# ArduOSD_Simple2222.net
KiCad netlist of a schematic drawn in EAGLE
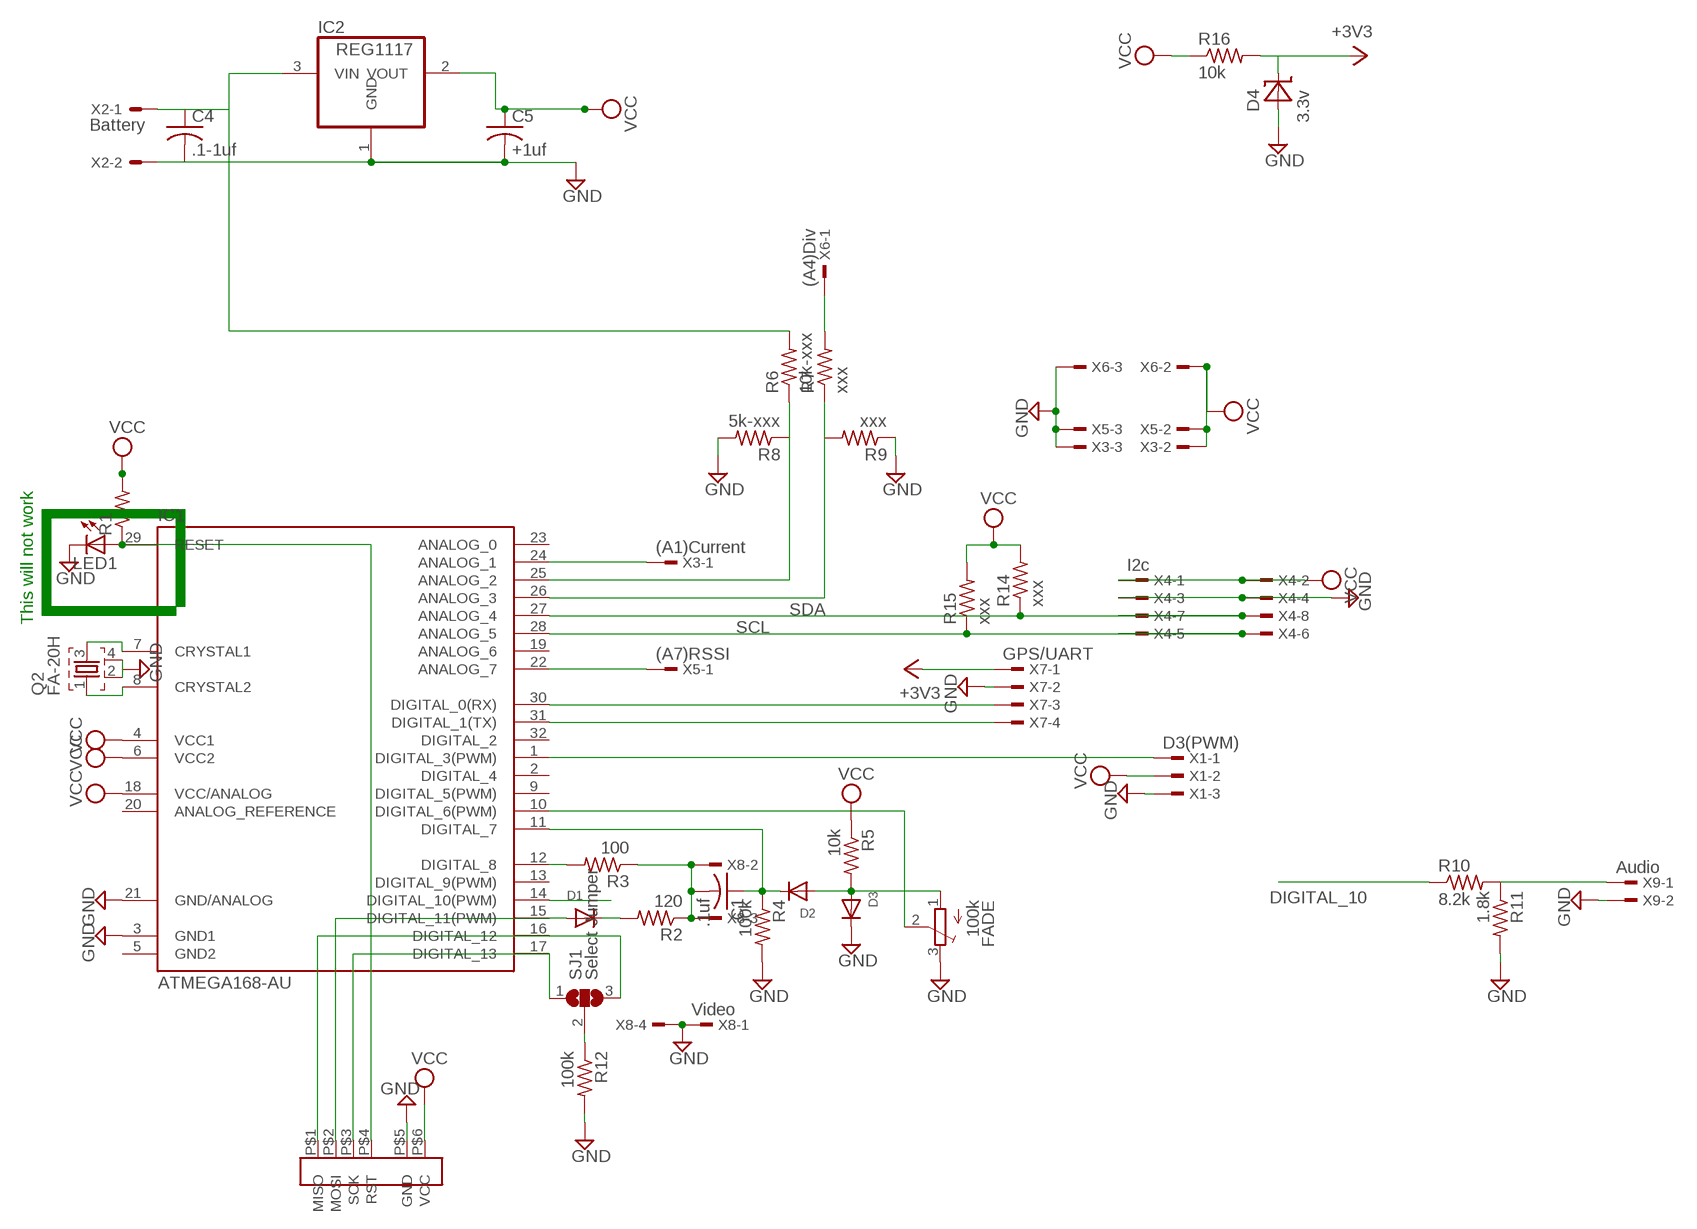
[diagram p0: schematic, sheet 1]

(export (version "E")
  (design (tool "Eeschema 10.0.6"))
  (components
    (comp (ref "C1")
      (value ".1uf")
      (footprint "eagle-import:C0805K")
      (libsource (lib "eagle-import") (part "C-USC0805K"))
    )
    (comp (ref "C4")
      (value ".1-1uf")
      (footprint "eagle-import:C0805K")
      (libsource (lib "eagle-import") (part "C-USC0805K"))
    )
    (comp (ref "C5")
      (value "+1uf")
      (footprint "eagle-import:C0805K")
      (libsource (lib "eagle-import") (part "C-USC0805K"))
    )
    (comp (ref "D1")
      (value "DIODESOT23_WAVE")
      (footprint "eagle-import:SOT23-W")
      (libsource (lib "eagle-import") (part "DIODESOT23_WAVE"))
    )
    (comp (ref "D2")
      (value "DIODESOT23_WAVE")
      (footprint "eagle-import:SOT23-W")
      (libsource (lib "eagle-import") (part "DIODESOT23_WAVE"))
    )
    (comp (ref "D3")
      (value "DIODESOT23_WAVE")
      (footprint "eagle-import:SOT23-W")
      (libsource (lib "eagle-import") (part "DIODESOT23_WAVE"))
    )
    (comp (ref "D4")
      (value "3.3v")
      (footprint "eagle-import:SOD-123")
      (libsource (lib "eagle-import") (part "ZENER_SOD123"))
    )
    (comp (ref "FADE")
      (value "100k")
      (footprint "eagle-import:TC33X")
      (libsource (lib "eagle-import") (part "TRIMPOTTC33X"))
    )
    (comp (ref "IC1")
      (value "ATMEGA168-AU")
      (footprint "eagle-import:TQFP32-08")
      (libsource (lib "eagle-import") (part "ATMEGA168-AU"))
    )
    (comp (ref "IC2")
      (value "REG1117")
      (footprint "eagle-import:SOT223")
      (libsource (lib "eagle-import") (part "REG1117"))
    )
    (comp (ref "LED1")
      (value "LEDCHIP-LED0805")
      (footprint "eagle-import:CHIP-LED0805")
      (libsource (lib "eagle-import") (part "LEDCHIP-LED0805"))
    )
    (comp (ref "Q2")
      (value "FA-20H")
      (footprint "eagle-import:FA-20H")
      (libsource (lib "eagle-import") (part "FA-20H"))
    )
    (comp (ref "R1")
      (value "R-US_R0805")
      (footprint "eagle-import:R0805")
      (libsource (lib "eagle-import") (part "R-US_R0805"))
    )
    (comp (ref "R2")
      (value "120")
      (footprint "eagle-import:R0805")
      (libsource (lib "eagle-import") (part "R-US_R0805"))
    )
    (comp (ref "R3")
      (value "100")
      (footprint "eagle-import:R0805")
      (libsource (lib "eagle-import") (part "R-US_R0805"))
    )
    (comp (ref "R4")
      (value "100k")
      (footprint "eagle-import:R0805")
      (libsource (lib "eagle-import") (part "R-US_R0805"))
    )
    (comp (ref "R5")
      (value "10k")
      (footprint "eagle-import:R0805")
      (libsource (lib "eagle-import") (part "R-US_R0805"))
    )
    (comp (ref "R6")
      (value "10k-xxx")
      (footprint "eagle-import:R0805")
      (libsource (lib "eagle-import") (part "R-US_R0805"))
    )
    (comp (ref "R7")
      (value "xxx")
      (footprint "eagle-import:R0805")
      (libsource (lib "eagle-import") (part "R-US_R0805"))
    )
    (comp (ref "R8")
      (value "5k-xxx")
      (footprint "eagle-import:R0805")
      (libsource (lib "eagle-import") (part "R-US_R0805"))
    )
    (comp (ref "R9")
      (value "xxx")
      (footprint "eagle-import:R0805")
      (libsource (lib "eagle-import") (part "R-US_R0805"))
    )
    (comp (ref "R10")
      (value "8.2k")
      (footprint "eagle-import:R0805")
      (libsource (lib "eagle-import") (part "R-US_R0805"))
    )
    (comp (ref "R11")
      (value "1.8k")
      (footprint "eagle-import:R0805")
      (libsource (lib "eagle-import") (part "R-US_R0805"))
    )
    (comp (ref "R12")
      (value "100k")
      (footprint "eagle-import:R0805")
      (libsource (lib "eagle-import") (part "R-US_R0805"))
    )
    (comp (ref "R14")
      (value "xxx")
      (footprint "eagle-import:R0805")
      (libsource (lib "eagle-import") (part "R-US_R0805"))
    )
    (comp (ref "R15")
      (value "xxx")
      (footprint "eagle-import:R0805")
      (libsource (lib "eagle-import") (part "R-US_R0805"))
    )
    (comp (ref "R16")
      (value "10k")
      (footprint "eagle-import:R0805")
      (libsource (lib "eagle-import") (part "R-US_R0805"))
    )
    (comp (ref "SJ1")
      (value "Select Jumper")
      (footprint "eagle-import:SJ_2")
      (libsource (lib "eagle-import") (part "SJ2W"))
    )
    (comp (ref "U$1")
      (value "LIN_ISP")
      (footprint "eagle-import:LINEAR_ISP")
      (libsource (lib "eagle-import") (part "LIN_ISP"))
    )
    (comp (ref "X1")
      (value "D3(PWM)")
      (footprint "eagle-import:TSW-103-02-S-S")
      (fields (field (name "OC_FARNELL") "unknown") (field (name "OC_NEWARK") "unknown"))
      (libsource (lib "eagle-import") (part "TSW-103-02-S-S"))
    )
    (comp (ref "X2")
      (value "Battery")
      (footprint "eagle-import:22-23-2021")
      (fields (field (name "MF") "MOLEX") (field (name "MPN") "22-23-2021"))
      (libsource (lib "eagle-import") (part "22-23-2021"))
    )
    (comp (ref "X3")
      (value "(A1)Current")
      (footprint "eagle-import:TSW-103-02-S-S")
      (libsource (lib "eagle-import") (part "TSW-103-02-S-S"))
    )
    (comp (ref "X4")
      (value "I2c")
      (footprint "eagle-import:TSW-104-02-S-D-RA")
      (libsource (lib "eagle-import") (part "TSW-104-02-S-D-RA"))
    )
    (comp (ref "X5")
      (value "(A7)RSSI")
      (footprint "eagle-import:TSW-103-02-S-S")
      (libsource (lib "eagle-import") (part "TSW-103-02-S-S"))
    )
    (comp (ref "X6")
      (value "(A4)Div")
      (footprint "eagle-import:TSW-103-02-S-S")
      (fields (field (name "OC_FARNELL") "unknown") (field (name "OC_NEWARK") "unknown"))
      (libsource (lib "eagle-import") (part "TSW-103-02-S-S"))
    )
    (comp (ref "X7")
      (value "GPS/UART")
      (footprint "eagle-import:TSW-104-02-S-S-RA")
      (libsource (lib "eagle-import") (part "TSW-104-02-S-S-RA"))
    )
    (comp (ref "X8")
      (value "Video")
      (footprint "eagle-import:TSW-104-02-S-S-RA")
      (libsource (lib "eagle-import") (part "TSW-104-02-S-S-RA"))
    )
    (comp (ref "X9")
      (value "Audio")
      (footprint "eagle-import:TSW-102-02-S-S-RA")
      (fields (field (name "OC_FARNELL") "unknown") (field (name "OC_NEWARK") "unknown"))
      (libsource (lib "eagle-import") (part "TSW-102-02-S-S-RA"))
    )
  )
  (nets
    (net (code "1") (name "+3V3") (class "Default")
      (node (ref "D4") (pin "1") (pinfunction "C_1") (pintype "passive"))
      (node (ref "R16") (pin "2") (pinfunction "2_2") (pintype "passive"))
      (node (ref "X7") (pin "1") (pinfunction "1_1") (pintype "passive"))
    )
    (net (code "2") (name "/DIGITAL_10") (class "Default")
      (node (ref "IC1") (pin "14") (pinfunction "DIGITAL_10(PWM)_14") (pintype "bidirectional"))
      (node (ref "R10") (pin "1") (pinfunction "1_1") (pintype "passive"))
    )
    (net (code "3") (name "/GND2") (class "Default")
      (node (ref "IC1") (pin "5") (pinfunction "GND2_5") (pintype "power_in"))
    )
    (net (code "4") (name "/SCL") (class "Default")
      (node (ref "IC1") (pin "28") (pinfunction "ANALOG_5_28") (pintype "bidirectional"))
      (node (ref "R15") (pin "1") (pinfunction "1_1") (pintype "passive"))
      (node (ref "X4") (pin "5") (pinfunction "1_5") (pintype "passive"))
      (node (ref "X4") (pin "6") (pinfunction "1_6") (pintype "passive"))
    )
    (net (code "5") (name "/SDA") (class "Default")
      (node (ref "IC1") (pin "27") (pinfunction "ANALOG_4_27") (pintype "bidirectional"))
      (node (ref "R14") (pin "1") (pinfunction "1_1") (pintype "passive"))
      (node (ref "X4") (pin "7") (pinfunction "1_7") (pintype "passive"))
      (node (ref "X4") (pin "8") (pinfunction "1_8") (pintype "passive"))
    )
    (net (code "6") (name "GND") (class "Default")
      (node (ref "C4") (pin "2") (pinfunction "2_2") (pintype "passive"))
      (node (ref "C5") (pin "2") (pinfunction "2_2") (pintype "passive"))
      (node (ref "D3") (pin "3") (pinfunction "C_3") (pintype "passive"))
      (node (ref "D4") (pin "2") (pinfunction "A_2") (pintype "passive"))
      (node (ref "FADE") (pin "3") (pinfunction "E_3") (pintype "passive"))
      (node (ref "IC1") (pin "21") (pinfunction "GND/ANALOG_21") (pintype "power_in"))
      (node (ref "IC1") (pin "3") (pinfunction "GND1_3") (pintype "power_in"))
      (node (ref "IC2") (pin "1") (pinfunction "GND_1") (pintype "power_in"))
      (node (ref "LED1") (pin "C") (pinfunction "C_C") (pintype "passive"))
      (node (ref "Q2") (pin "2") (pinfunction "2_2") (pintype "passive"))
      (node (ref "Q2") (pin "4") (pinfunction "4_4") (pintype "passive"))
      (node (ref "R11") (pin "2") (pinfunction "2_2") (pintype "passive"))
      (node (ref "R12") (pin "2") (pinfunction "2_2") (pintype "passive"))
      (node (ref "R4") (pin "2") (pinfunction "2_2") (pintype "passive"))
      (node (ref "R8") (pin "2") (pinfunction "2_2") (pintype "passive"))
      (node (ref "R9") (pin "1") (pinfunction "1_1") (pintype "passive"))
      (node (ref "U$1") (pin "P$5") (pinfunction "GND_P$5") (pintype "bidirectional"))
      (node (ref "X1") (pin "3") (pinfunction "1_3") (pintype "passive"))
      (node (ref "X2") (pin "2") (pinfunction "S_2") (pintype "passive"))
      (node (ref "X3") (pin "3") (pinfunction "1_3") (pintype "passive"))
      (node (ref "X4") (pin "3") (pinfunction "1_3") (pintype "passive"))
      (node (ref "X4") (pin "4") (pinfunction "1_4") (pintype "passive"))
      (node (ref "X5") (pin "3") (pinfunction "1_3") (pintype "passive"))
      (node (ref "X6") (pin "3") (pinfunction "1_3") (pintype "passive"))
      (node (ref "X7") (pin "2") (pinfunction "1_2") (pintype "passive"))
      (node (ref "X8") (pin "1") (pinfunction "1_1") (pintype "passive"))
      (node (ref "X8") (pin "4") (pinfunction "1_4") (pintype "passive"))
      (node (ref "X9") (pin "2") (pinfunction "1_2") (pintype "passive"))
    )
    (net (code "7") (name "Net-(D1-A)") (class "Default")
      (node (ref "D1") (pin "1") (pinfunction "A_1") (pintype "passive"))
      (node (ref "IC1") (pin "15") (pinfunction "DIGITAL_11(PWM)_15") (pintype "bidirectional"))
      (node (ref "U$1") (pin "P$2") (pinfunction "MOSI_P$2") (pintype "bidirectional"))
    )
    (net (code "8") (name "Net-(D1-C)") (class "Default")
      (node (ref "D1") (pin "3") (pinfunction "C_3") (pintype "passive"))
      (node (ref "R2") (pin "2") (pinfunction "2_2") (pintype "passive"))
    )
    (net (code "9") (name "Net-(D2-A)") (class "Default")
      (node (ref "D2") (pin "1") (pinfunction "A_1") (pintype "passive"))
      (node (ref "D3") (pin "1") (pinfunction "A_1") (pintype "passive"))
      (node (ref "FADE") (pin "1") (pinfunction "A_1") (pintype "passive"))
      (node (ref "R5") (pin "2") (pinfunction "2_2") (pintype "passive"))
    )
    (net (code "10") (name "Net-(D2-C)") (class "Default")
      (node (ref "C1") (pin "1") (pinfunction "1_1") (pintype "passive"))
      (node (ref "D2") (pin "3") (pinfunction "C_3") (pintype "passive"))
      (node (ref "IC1") (pin "11") (pinfunction "DIGITAL_7_11") (pintype "bidirectional"))
      (node (ref "R4") (pin "1") (pinfunction "1_1") (pintype "passive"))
    )
    (net (code "11") (name "Net-(FADE-S)") (class "Default")
      (node (ref "FADE") (pin "2") (pinfunction "S_2") (pintype "passive"))
      (node (ref "IC1") (pin "10") (pinfunction "DIGITAL_6(PWM)_10") (pintype "bidirectional"))
    )
    (net (code "12") (name "Net-(IC1-ANALOG_1)") (class "Default")
      (node (ref "IC1") (pin "24") (pinfunction "ANALOG_1_24") (pintype "bidirectional"))
      (node (ref "X3") (pin "1") (pinfunction "1_1") (pintype "passive"))
    )
    (net (code "13") (name "Net-(IC1-ANALOG_2)") (class "Default")
      (node (ref "IC1") (pin "25") (pinfunction "ANALOG_2_25") (pintype "bidirectional"))
      (node (ref "R6") (pin "1") (pinfunction "1_1") (pintype "passive"))
      (node (ref "R8") (pin "1") (pinfunction "1_1") (pintype "passive"))
    )
    (net (code "14") (name "Net-(IC1-ANALOG_3)") (class "Default")
      (node (ref "IC1") (pin "26") (pinfunction "ANALOG_3_26") (pintype "bidirectional"))
      (node (ref "R7") (pin "1") (pinfunction "1_1") (pintype "passive"))
      (node (ref "R9") (pin "2") (pinfunction "2_2") (pintype "passive"))
    )
    (net (code "15") (name "Net-(IC1-ANALOG_7)") (class "Default")
      (node (ref "IC1") (pin "22") (pinfunction "ANALOG_7_22") (pintype "passive"))
      (node (ref "X5") (pin "1") (pinfunction "1_1") (pintype "passive"))
    )
    (net (code "16") (name "Net-(IC1-CRYSTAL1)") (class "Default")
      (node (ref "IC1") (pin "7") (pinfunction "CRYSTAL1_7") (pintype "bidirectional"))
      (node (ref "Q2") (pin "3") (pinfunction "3_3") (pintype "passive"))
    )
    (net (code "17") (name "Net-(IC1-CRYSTAL2)") (class "Default")
      (node (ref "IC1") (pin "8") (pinfunction "CRYSTAL2_8") (pintype "bidirectional"))
      (node (ref "Q2") (pin "1") (pinfunction "1_1") (pintype "passive"))
    )
    (net (code "18") (name "Net-(IC1-DIGITAL_0(RX))") (class "Default")
      (node (ref "IC1") (pin "30") (pinfunction "DIGITAL_0(RX)_30") (pintype "bidirectional"))
      (node (ref "X7") (pin "3") (pinfunction "1_3") (pintype "passive"))
    )
    (net (code "19") (name "Net-(IC1-DIGITAL_1(TX))") (class "Default")
      (node (ref "IC1") (pin "31") (pinfunction "DIGITAL_1(TX)_31") (pintype "bidirectional"))
      (node (ref "X7") (pin "4") (pinfunction "1_4") (pintype "passive"))
    )
    (net (code "20") (name "Net-(IC1-DIGITAL_3(PWM))") (class "Default")
      (node (ref "IC1") (pin "1") (pinfunction "DIGITAL_3(PWM)_1") (pintype "bidirectional"))
      (node (ref "X1") (pin "1") (pinfunction "1_1") (pintype "passive"))
    )
    (net (code "21") (name "Net-(IC1-DIGITAL_8)") (class "Default")
      (node (ref "IC1") (pin "12") (pinfunction "DIGITAL_8_12") (pintype "bidirectional"))
      (node (ref "R3") (pin "2") (pinfunction "2_2") (pintype "passive"))
    )
    (net (code "22") (name "Net-(IC1-DIGITAL_12)") (class "Default")
      (node (ref "IC1") (pin "16") (pinfunction "DIGITAL_12_16") (pintype "bidirectional"))
      (node (ref "SJ1") (pin "3") (pinfunction "3_3") (pintype "passive"))
      (node (ref "U$1") (pin "P$1") (pinfunction "MISO_P$1") (pintype "bidirectional"))
    )
    (net (code "23") (name "Net-(IC1-DIGITAL_13)") (class "Default")
      (node (ref "IC1") (pin "17") (pinfunction "DIGITAL_13_17") (pintype "bidirectional"))
      (node (ref "SJ1") (pin "1") (pinfunction "1_1") (pintype "passive"))
      (node (ref "U$1") (pin "P$3") (pinfunction "SCK_P$3") (pintype "bidirectional"))
    )
    (net (code "24") (name "Net-(IC1-RESET)") (class "Default")
      (node (ref "IC1") (pin "29") (pinfunction "RESET_29") (pintype "bidirectional"))
      (node (ref "LED1") (pin "A") (pinfunction "A_A") (pintype "passive"))
      (node (ref "R1") (pin "1") (pinfunction "1_1") (pintype "passive"))
      (node (ref "U$1") (pin "P$4") (pinfunction "RST_P$4") (pintype "bidirectional"))
    )
    (net (code "25") (name "Net-(IC2-VIN)") (class "Default")
      (node (ref "C4") (pin "1") (pinfunction "1_1") (pintype "passive"))
      (node (ref "IC2") (pin "3") (pinfunction "VIN_3") (pintype "input"))
      (node (ref "R6") (pin "2") (pinfunction "2_2") (pintype "passive"))
      (node (ref "X2") (pin "1") (pinfunction "S_1") (pintype "passive"))
    )
    (net (code "26") (name "Net-(R7-Pad2)") (class "Default")
      (node (ref "R7") (pin "2") (pinfunction "2_2") (pintype "passive"))
      (node (ref "X6") (pin "1") (pinfunction "1_1") (pintype "passive"))
    )
    (net (code "27") (name "Net-(R10-Pad2)") (class "Default")
      (node (ref "R10") (pin "2") (pinfunction "2_2") (pintype "passive"))
      (node (ref "R11") (pin "1") (pinfunction "1_1") (pintype "passive"))
      (node (ref "X9") (pin "1") (pinfunction "1_1") (pintype "passive"))
    )
    (net (code "28") (name "Net-(R12-Pad1)") (class "Default")
      (node (ref "R12") (pin "1") (pinfunction "1_1") (pintype "passive"))
      (node (ref "SJ1") (pin "2") (pinfunction "2_2") (pintype "passive"))
    )
    (net (code "29") (name "Net-(X8B-1)") (class "Default")
      (node (ref "C1") (pin "2") (pinfunction "2_2") (pintype "passive"))
      (node (ref "R2") (pin "1") (pinfunction "1_1") (pintype "passive"))
      (node (ref "R3") (pin "1") (pinfunction "1_1") (pintype "passive"))
      (node (ref "X8") (pin "2") (pinfunction "1_2") (pintype "passive"))
      (node (ref "X8") (pin "3") (pinfunction "1_3") (pintype "passive"))
    )
    (net (code "30") (name "VCC") (class "Default")
      (node (ref "C5") (pin "1") (pinfunction "1_1") (pintype "passive"))
      (node (ref "IC1") (pin "18") (pinfunction "VCC/ANALOG_18") (pintype "passive"))
      (node (ref "IC1") (pin "4") (pinfunction "VCC1_4") (pintype "power_in"))
      (node (ref "IC1") (pin "6") (pinfunction "VCC2_6") (pintype "power_in"))
      (node (ref "IC2") (pin "2") (pinfunction "VOUT_2") (pintype "output"))
      (node (ref "R1") (pin "2") (pinfunction "2_2") (pintype "passive"))
      (node (ref "R14") (pin "2") (pinfunction "2_2") (pintype "passive"))
      (node (ref "R15") (pin "2") (pinfunction "2_2") (pintype "passive"))
      (node (ref "R16") (pin "1") (pinfunction "1_1") (pintype "passive"))
      (node (ref "R5") (pin "1") (pinfunction "1_1") (pintype "passive"))
      (node (ref "U$1") (pin "P$6") (pinfunction "VCC_P$6") (pintype "bidirectional"))
      (node (ref "X1") (pin "2") (pinfunction "1_2") (pintype "passive"))
      (node (ref "X3") (pin "2") (pinfunction "1_2") (pintype "passive"))
      (node (ref "X4") (pin "1") (pinfunction "1_1") (pintype "passive"))
      (node (ref "X4") (pin "2") (pinfunction "1_2") (pintype "passive"))
      (node (ref "X5") (pin "2") (pinfunction "1_2") (pintype "passive"))
      (node (ref "X6") (pin "2") (pinfunction "1_2") (pintype "passive"))
    )
    (net (code "31") (name "unconnected-(IC1-ANALOG_0-Pad23)") (class "Default")
      (node (ref "IC1") (pin "23") (pinfunction "ANALOG_0_23") (pintype "bidirectional"))
    )
    (net (code "32") (name "unconnected-(IC1-ANALOG_6-Pad19)") (class "Default")
      (node (ref "IC1") (pin "19") (pinfunction "ANALOG_6_19") (pintype "passive"))
    )
    (net (code "33") (name "unconnected-(IC1-ANALOG_REFERENCE-Pad20)") (class "Default")
      (node (ref "IC1") (pin "20") (pinfunction "ANALOG_REFERENCE_20") (pintype "passive"))
    )
    (net (code "34") (name "unconnected-(IC1-DIGITAL_2-Pad32)") (class "Default")
      (node (ref "IC1") (pin "32") (pinfunction "DIGITAL_2_32") (pintype "bidirectional"))
    )
    (net (code "35") (name "unconnected-(IC1-DIGITAL_4-Pad2)") (class "Default")
      (node (ref "IC1") (pin "2") (pinfunction "DIGITAL_4_2") (pintype "bidirectional"))
    )
    (net (code "36") (name "unconnected-(IC1-DIGITAL_5(PWM)-Pad9)") (class "Default")
      (node (ref "IC1") (pin "9") (pinfunction "DIGITAL_5(PWM)_9") (pintype "bidirectional"))
    )
    (net (code "37") (name "unconnected-(IC1-DIGITAL_9(PWM)-Pad13)") (class "Default")
      (node (ref "IC1") (pin "13") (pinfunction "DIGITAL_9(PWM)_13") (pintype "bidirectional"))
    )
  )
)
